# untitled.net
KiCad netlist of a schematic drawn in EAGLE
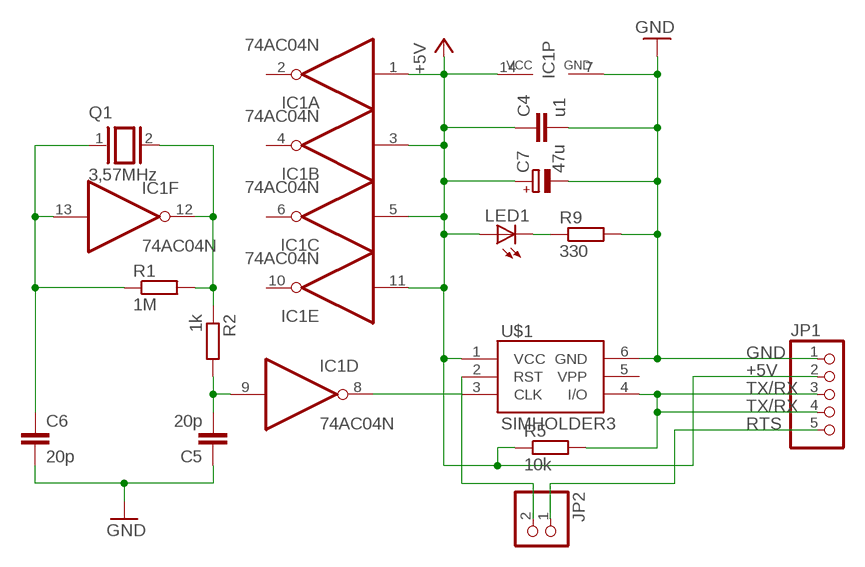
[diagram p0: schematic, sheet 1]

(export (version "E")
  (design (tool "Eeschema 10.0.6"))
  (components
    (comp (ref "C4")
      (value "u1")
      (footprint "eagle-import:C025-025X050")
      (libsource (lib "eagle-import") (part "C-EU025-025X050"))
    )
    (comp (ref "C5")
      (value "20p")
      (footprint "eagle-import:C025-025X050")
      (libsource (lib "eagle-import") (part "C-EU025-025X050"))
    )
    (comp (ref "C6")
      (value "20p")
      (footprint "eagle-import:C025-025X050")
      (libsource (lib "eagle-import") (part "C-EU025-025X050"))
    )
    (comp (ref "C7")
      (value "47u")
      (footprint "eagle-import:E2,5-6E")
      (libsource (lib "eagle-import") (part "CPOL-EUE2,5-6E"))
    )
    (comp (ref "IC1")
      (value "74AC04N")
      (footprint "eagle-import:DIL14")
      (libsource (lib "eagle-import") (part "7404NAC"))
    )
    (comp (ref "JP1")
      (value "PINHD-1X5/90")
      (footprint "eagle-import:1X05_90")
      (libsource (lib "eagle-import") (part "PINHD-1X5/90"))
    )
    (comp (ref "JP2")
      (value "PINHD-1X2")
      (footprint "eagle-import:1X02")
      (libsource (lib "eagle-import") (part "PINHD-1X2"))
    )
    (comp (ref "LED1")
      (value "LED3MM")
      (footprint "eagle-import:LED3MM")
      (libsource (lib "eagle-import") (part "LED3MM"))
    )
    (comp (ref "Q1")
      (value "3,57MHz")
      (footprint "eagle-import:QS")
      (libsource (lib "eagle-import") (part "XTAL/S"))
    )
    (comp (ref "R1")
      (value "1M")
      (footprint "eagle-import:0207_2V")
      (libsource (lib "eagle-import") (part "R-EU_0207/2V"))
    )
    (comp (ref "R2")
      (value "1k")
      (footprint "eagle-import:0207_2V")
      (libsource (lib "eagle-import") (part "R-EU_0207/2V"))
    )
    (comp (ref "R5")
      (value "10k")
      (footprint "eagle-import:0207_2V")
      (libsource (lib "eagle-import") (part "R-EU_0207/2V"))
    )
    (comp (ref "R9")
      (value "330")
      (footprint "eagle-import:0207_2V")
      (libsource (lib "eagle-import") (part "R-EU_0207/2V"))
    )
    (comp (ref "U$1")
      (value "SIMHOLDER3")
      (footprint "eagle-import:SIMHOLDER3")
      (libsource (lib "eagle-import") (part "SIMHOLDER3"))
    )
  )
  (nets
    (net (code "1") (name "+5V") (class "Default")
      (node (ref "C4") (pin "1") (pinfunction "1_1") (pintype "passive"))
      (node (ref "C7") (pin "+") (pinfunction "+_+") (pintype "passive"))
      (node (ref "IC1") (pin "1") (pinfunction "I_1") (pintype "input"))
      (node (ref "IC1") (pin "11") (pinfunction "I_11") (pintype "input"))
      (node (ref "IC1") (pin "14") (pinfunction "VCC_14") (pintype "power_in"))
      (node (ref "IC1") (pin "3") (pinfunction "I_3") (pintype "input"))
      (node (ref "IC1") (pin "5") (pinfunction "I_5") (pintype "input"))
      (node (ref "JP1") (pin "2") (pinfunction "2_2") (pintype "passive"))
      (node (ref "LED1") (pin "A") (pinfunction "A_A") (pintype "passive"))
      (node (ref "R5") (pin "1") (pinfunction "1_1") (pintype "passive"))
      (node (ref "U$1") (pin "1") (pinfunction "VCC_1") (pintype "bidirectional"))
    )
    (net (code "2") (name "/RTS") (class "Default")
      (node (ref "JP1") (pin "5") (pinfunction "5_5") (pintype "passive"))
      (node (ref "JP2") (pin "1") (pinfunction "1_1") (pintype "passive"))
    )
    (net (code "3") (name "/TX{slash}RX") (class "Default")
      (node (ref "JP1") (pin "3") (pinfunction "3_3") (pintype "passive"))
      (node (ref "JP1") (pin "4") (pinfunction "4_4") (pintype "passive"))
      (node (ref "R5") (pin "2") (pinfunction "2_2") (pintype "passive"))
      (node (ref "U$1") (pin "4") (pinfunction "I/O_4") (pintype "bidirectional"))
    )
    (net (code "4") (name "GND") (class "Default")
      (node (ref "C4") (pin "2") (pinfunction "2_2") (pintype "passive"))
      (node (ref "C5") (pin "1") (pinfunction "1_1") (pintype "passive"))
      (node (ref "C6") (pin "2") (pinfunction "2_2") (pintype "passive"))
      (node (ref "C7") (pin "-") (pinfunction "-_-") (pintype "passive"))
      (node (ref "IC1") (pin "7") (pinfunction "GND_7") (pintype "power_in"))
      (node (ref "JP1") (pin "1") (pinfunction "1_1") (pintype "passive"))
      (node (ref "R9") (pin "2") (pinfunction "2_2") (pintype "passive"))
      (node (ref "U$1") (pin "6") (pinfunction "GND_6") (pintype "bidirectional"))
    )
    (net (code "5") (name "Net-(IC1D-I)") (class "Default")
      (node (ref "C5") (pin "2") (pinfunction "2_2") (pintype "passive"))
      (node (ref "IC1") (pin "9") (pinfunction "I_9") (pintype "input"))
      (node (ref "R2") (pin "2") (pinfunction "2_2") (pintype "passive"))
    )
    (net (code "6") (name "Net-(IC1D-O)") (class "Default")
      (node (ref "IC1") (pin "8") (pinfunction "O_8") (pintype "output"))
      (node (ref "U$1") (pin "3") (pinfunction "CLK_3") (pintype "bidirectional"))
    )
    (net (code "7") (name "Net-(IC1F-I)") (class "Default")
      (node (ref "C6") (pin "1") (pinfunction "1_1") (pintype "passive"))
      (node (ref "IC1") (pin "13") (pinfunction "I_13") (pintype "input"))
      (node (ref "Q1") (pin "1") (pinfunction "1_1") (pintype "passive"))
      (node (ref "R1") (pin "1") (pinfunction "1_1") (pintype "passive"))
    )
    (net (code "8") (name "Net-(IC1F-O)") (class "Default")
      (node (ref "IC1") (pin "12") (pinfunction "O_12") (pintype "output"))
      (node (ref "Q1") (pin "2") (pinfunction "2_2") (pintype "passive"))
      (node (ref "R1") (pin "2") (pinfunction "2_2") (pintype "passive"))
      (node (ref "R2") (pin "1") (pinfunction "1_1") (pintype "passive"))
    )
    (net (code "9") (name "Net-(LED1-C)") (class "Default")
      (node (ref "LED1") (pin "K") (pinfunction "C_K") (pintype "passive"))
      (node (ref "R9") (pin "1") (pinfunction "1_1") (pintype "passive"))
    )
    (net (code "10") (name "Net-(U$1-RST)") (class "Default")
      (node (ref "JP2") (pin "2") (pinfunction "2_2") (pintype "passive"))
      (node (ref "U$1") (pin "2") (pinfunction "RST_2") (pintype "bidirectional"))
    )
    (net (code "11") (name "unconnected-(IC1A-O-Pad2)") (class "Default")
      (node (ref "IC1") (pin "2") (pinfunction "O_2") (pintype "output"))
    )
    (net (code "12") (name "unconnected-(IC1B-O-Pad4)") (class "Default")
      (node (ref "IC1") (pin "4") (pinfunction "O_4") (pintype "output"))
    )
    (net (code "13") (name "unconnected-(IC1C-O-Pad6)") (class "Default")
      (node (ref "IC1") (pin "6") (pinfunction "O_6") (pintype "output"))
    )
    (net (code "14") (name "unconnected-(IC1E-O-Pad10)") (class "Default")
      (node (ref "IC1") (pin "10") (pinfunction "O_10") (pintype "output"))
    )
    (net (code "15") (name "unconnected-(U$1-VPP-Pad5)") (class "Default")
      (node (ref "U$1") (pin "5") (pinfunction "VPP_5") (pintype "bidirectional"))
    )
  )
)
